# sch_substrate_board_pwr.net
KiCad netlist of a schematic drawn in Altium Designer
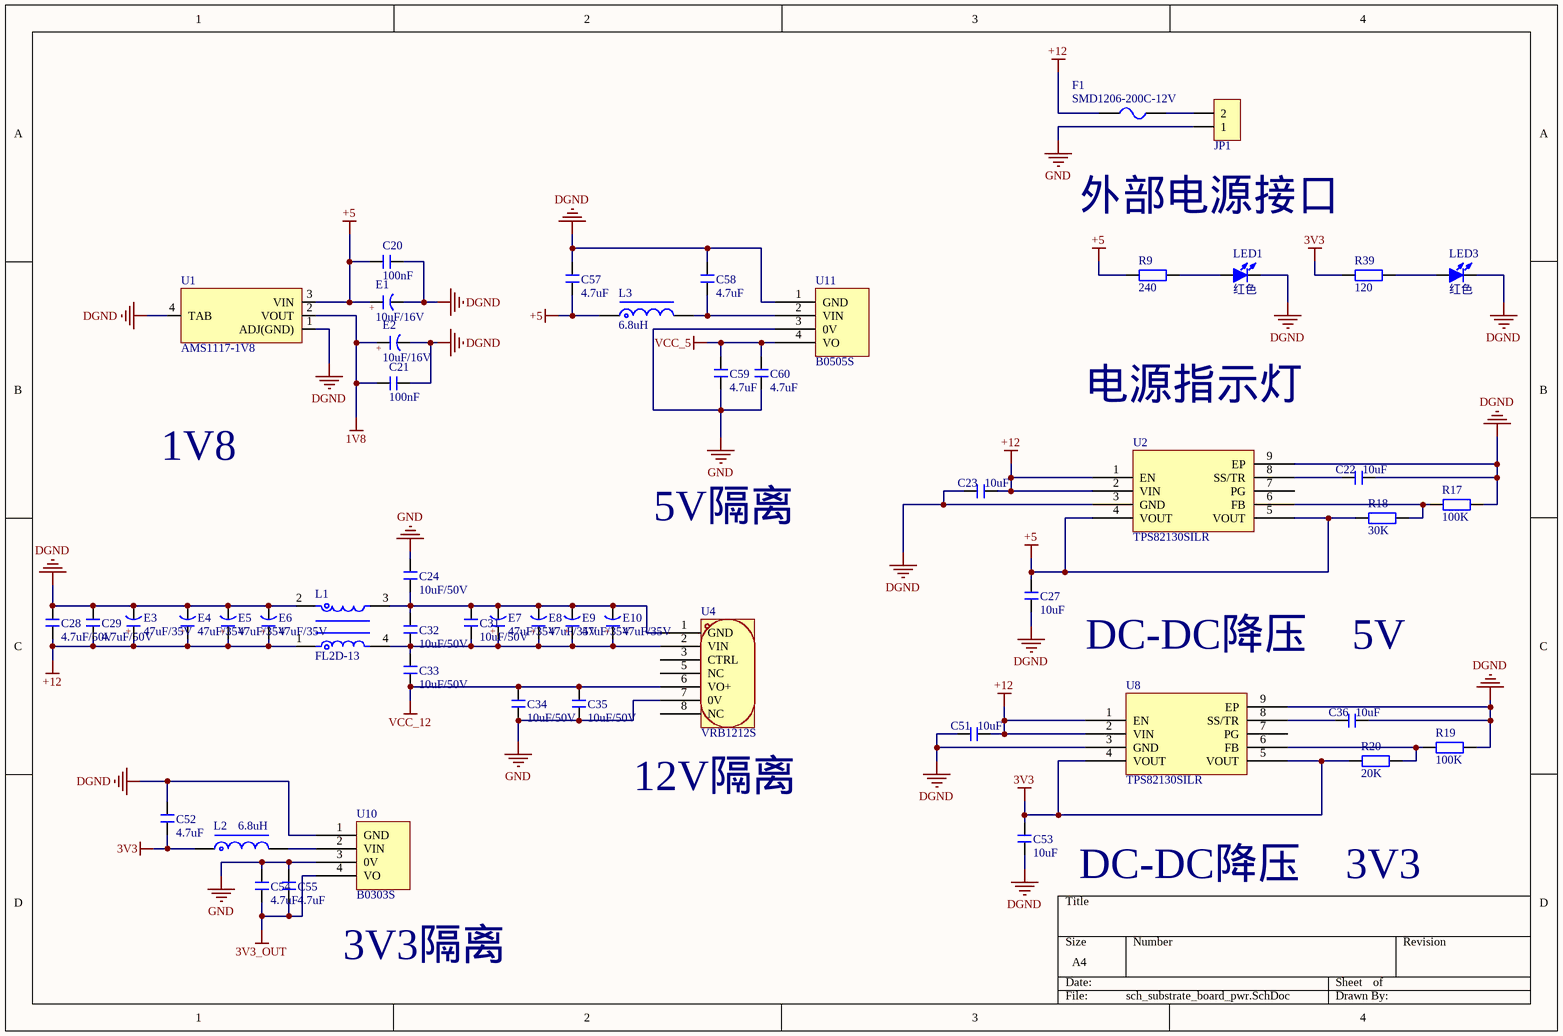
[diagram p0: sch_substrate_board_pwr.SchDoc]

(export (version "E")
  (design (tool "Eeschema 10.0.6"))
  (components
    (comp (ref "C20")
      (value "100nF")
      (footprint "C 0805_L")
      (description "贴片电容")
      (libsource (lib "0.1 - 电阻-电容-电感") (part "C"))
    )
    (comp (ref "C21")
      (value "100nF")
      (footprint "C 0805_L")
      (description "贴片电容")
      (libsource (lib "0.1 - 电阻-电容-电感") (part "C"))
    )
    (comp (ref "C22")
      (value "10uF")
      (footprint "C 0805_L")
      (description "贴片电容")
      (libsource (lib "0.1 - 电阻-电容-电感") (part "C"))
    )
    (comp (ref "C23")
      (value "10uF")
      (footprint "C 0805_L")
      (description "贴片电容")
      (libsource (lib "0.1 - 电阻-电容-电感") (part "C"))
    )
    (comp (ref "C24")
      (value "10uF/50V")
      (footprint "CAP-SMD_L8.0-W6.0-LS11.4")
      (description "贴片电容")
      (libsource (lib "0.1 - 电阻-电容-电感") (part "C"))
    )
    (comp (ref "C27")
      (value "10uF")
      (footprint "C 0805_L")
      (description "贴片电容")
      (libsource (lib "0.1 - 电阻-电容-电感") (part "C"))
    )
    (comp (ref "C28")
      (value "4.7uF/50V")
      (footprint "C 0805_L")
      (description "贴片电容")
      (libsource (lib "0.1 - 电阻-电容-电感") (part "C"))
    )
    (comp (ref "C29")
      (value "4.7uF/50V")
      (footprint "C 0805_L")
      (description "贴片电容")
      (libsource (lib "0.1 - 电阻-电容-电感") (part "C"))
    )
    (comp (ref "C31")
      (value "10uF/50V")
      (footprint "C 0805_L")
      (description "贴片电容")
      (libsource (lib "0.1 - 电阻-电容-电感") (part "C"))
    )
    (comp (ref "C32")
      (value "10uF/50V")
      (footprint "C 0805_L")
      (description "贴片电容")
      (libsource (lib "0.1 - 电阻-电容-电感") (part "C"))
    )
    (comp (ref "C33")
      (value "10uF/50V")
      (footprint "CAP-SMD_L8.0-W6.0-LS11.4")
      (description "贴片电容")
      (libsource (lib "0.1 - 电阻-电容-电感") (part "C"))
    )
    (comp (ref "C34")
      (value "10uF/50V")
      (footprint "C 0805_L")
      (description "贴片电容")
      (libsource (lib "0.1 - 电阻-电容-电感") (part "C"))
    )
    (comp (ref "C35")
      (value "10uF/50V")
      (footprint "C 0805_L")
      (description "贴片电容")
      (libsource (lib "0.1 - 电阻-电容-电感") (part "C"))
    )
    (comp (ref "C36")
      (value "10uF")
      (footprint "C 0805_L")
      (description "贴片电容")
      (libsource (lib "0.1 - 电阻-电容-电感") (part "C"))
    )
    (comp (ref "C51")
      (value "10uF")
      (footprint "C 0805_L")
      (description "贴片电容")
      (libsource (lib "0.1 - 电阻-电容-电感") (part "C"))
    )
    (comp (ref "C52")
      (value "4.7uF")
      (footprint "C 0805_L")
      (description "贴片电容")
      (libsource (lib "0.1 - 电阻-电容-电感") (part "C"))
    )
    (comp (ref "C53")
      (value "10uF")
      (footprint "C 0805_L")
      (description "贴片电容")
      (libsource (lib "0.1 - 电阻-电容-电感") (part "C"))
    )
    (comp (ref "C54")
      (value "4.7uF")
      (footprint "C 0805_L")
      (description "贴片电容")
      (libsource (lib "0.1 - 电阻-电容-电感") (part "C"))
    )
    (comp (ref "C55")
      (value "4.7uF")
      (footprint "C 0805_L")
      (description "贴片电容")
      (libsource (lib "0.1 - 电阻-电容-电感") (part "C"))
    )
    (comp (ref "C57")
      (value "4.7uF")
      (footprint "C 0805_L")
      (description "贴片电容")
      (libsource (lib "0.1 - 电阻-电容-电感") (part "C"))
    )
    (comp (ref "C58")
      (value "4.7uF")
      (footprint "C 0805_L")
      (description "贴片电容")
      (libsource (lib "0.1 - 电阻-电容-电感") (part "C"))
    )
    (comp (ref "C59")
      (value "4.7uF")
      (footprint "C 0805_L")
      (description "贴片电容")
      (libsource (lib "0.1 - 电阻-电容-电感") (part "C"))
    )
    (comp (ref "C60")
      (value "4.7uF")
      (footprint "C 0805_L")
      (description "贴片电容")
      (libsource (lib "0.1 - 电阻-电容-电感") (part "C"))
    )
    (comp (ref "E1")
      (value "10uF/16V")
      (footprint "CD A(3216)")
      (description "贴片钽电容")
      (libsource (lib "") (part "CT_1"))
    )
    (comp (ref "E2")
      (value "10uF/16V")
      (footprint "CD A(3216)")
      (description "贴片钽电容")
      (libsource (lib "") (part "CT_1"))
    )
    (comp (ref "E3")
      (value "47uF/35V")
      (footprint "CD D(7343)")
      (description "贴片钽电容")
      (libsource (lib "0.1 - 电阻-电容-电感") (part "CT"))
    )
    (comp (ref "E4")
      (value "47uF/35V")
      (footprint "CD D(7343)")
      (description "贴片钽电容")
      (libsource (lib "0.1 - 电阻-电容-电感") (part "CT"))
    )
    (comp (ref "E5")
      (value "47uF/35V")
      (footprint "CD D(7343)")
      (description "贴片钽电容")
      (libsource (lib "0.1 - 电阻-电容-电感") (part "CT"))
    )
    (comp (ref "E6")
      (value "47uF/35V")
      (footprint "CD D(7343)")
      (description "贴片钽电容")
      (libsource (lib "0.1 - 电阻-电容-电感") (part "CT"))
    )
    (comp (ref "E7")
      (value "47uF/35V")
      (footprint "CD D(7343)")
      (description "贴片钽电容")
      (libsource (lib "0.1 - 电阻-电容-电感") (part "CT"))
    )
    (comp (ref "E8")
      (value "47uF/35V")
      (footprint "CD D(7343)")
      (description "贴片钽电容")
      (libsource (lib "0.1 - 电阻-电容-电感") (part "CT"))
    )
    (comp (ref "E9")
      (value "47uF/35V")
      (footprint "CD D(7343)")
      (description "贴片钽电容")
      (libsource (lib "0.1 - 电阻-电容-电感") (part "CT"))
    )
    (comp (ref "E10")
      (value "47uF/35V")
      (footprint "CD D(7343)")
      (description "贴片钽电容")
      (libsource (lib "0.1 - 电阻-电容-电感") (part "CT"))
    )
    (comp (ref "F1")
      (value "SMD1206-200C-12V")
      (footprint "FU 1206")
      (description "贴片保险丝")
      (fields (field (name "版权归属") "封装库来自淘宝卖家 ID：黄晶宝石"))
      (libsource (lib "2.0 - 保险丝-晶振-光耦") (part "FU"))
    )
    (comp (ref "JP1")
      (value "HDR-1X2")
      (footprint "KF350-2P")
      (description "2P接插件")
      (fields (field (name "版权归属") "封装库来自淘宝卖家 ID：黄晶宝石"))
      (libsource (lib "5.5 - 接插件-脚距3.5") (part "Header 2"))
    )
    (comp (ref "L1")
      (value "FL2D-13")
      (footprint "FL2D-13")
      (description "共模滤波器")
      (libsource (lib "schlib_substrate") (part "FL2D-13"))
    )
    (comp (ref "L2")
      (value "6.8uH")
      (footprint "- duplicate")
      (description "功率磁环电感")
      (libsource (lib "0.1 - 电阻-电容-电感") (part "L-MR"))
    )
    (comp (ref "L3")
      (value "6.8uH")
      (footprint "- duplicate")
      (description "功率磁环电感")
      (libsource (lib "0.1 - 电阻-电容-电感") (part "L-MR"))
    )
    (comp (ref "LED1")
      (value "红色")
      (footprint "LED 0805R")
      (description "贴片LED")
      (fields (field (name "版权归属") "封装库来自淘宝 ID：黄晶宝石"))
      (libsource (lib "0.3 - LED发光二极管") (part "LED-SMD"))
    )
    (comp (ref "LED3")
      (value "红色")
      (footprint "LED 0805R")
      (description "贴片LED")
      (fields (field (name "版权归属") "封装库来自淘宝 ID：黄晶宝石"))
      (libsource (lib "0.3 - LED发光二极管") (part "LED-SMD"))
    )
    (comp (ref "R9")
      (value "240")
      (footprint "R 0805_L")
      (description "贴片电阻")
      (fields (field (name "版权归属") "来自淘宝 ID：黄晶宝石"))
      (libsource (lib "0.1 - 电阻-电容-电感") (part "R"))
    )
    (comp (ref "R17")
      (value "100K")
      (footprint "R 0805_L")
      (description "贴片电阻")
      (fields (field (name "版权归属") "来自淘宝 ID：黄晶宝石"))
      (libsource (lib "0.1 - 电阻-电容-电感") (part "R"))
    )
    (comp (ref "R18")
      (value "30K")
      (footprint "R 0805_L")
      (description "贴片电阻")
      (fields (field (name "版权归属") "来自淘宝 ID：黄晶宝石"))
      (libsource (lib "0.1 - 电阻-电容-电感") (part "R"))
    )
    (comp (ref "R19")
      (value "100K")
      (footprint "R 0805_L")
      (description "贴片电阻")
      (fields (field (name "版权归属") "来自淘宝 ID：黄晶宝石"))
      (libsource (lib "0.1 - 电阻-电容-电感") (part "R"))
    )
    (comp (ref "R20")
      (value "20K")
      (footprint "R 0805_L")
      (description "贴片电阻")
      (fields (field (name "版权归属") "来自淘宝 ID：黄晶宝石"))
      (libsource (lib "0.1 - 电阻-电容-电感") (part "R"))
    )
    (comp (ref "R39")
      (value "120")
      (footprint "R 0805_L")
      (description "贴片电阻")
      (fields (field (name "版权归属") "来自淘宝 ID：黄晶宝石"))
      (libsource (lib "0.1 - 电阻-电容-电感") (part "R"))
    )
    (comp (ref "U1")
      (value "AMS1117-1V8")
      (footprint "AMS1117")
      (description "电源稳压芯片")
      (libsource (lib "schlib_substrate") (part "AMS1117"))
    )
    (comp (ref "U2")
      (value "TPS82130SILR")
      (footprint "TPS82130SILR")
      (description "DC-DC")
      (libsource (lib "schlib_substrate") (part "TPS82130SILR"))
    )
    (comp (ref "U4")
      (value "VRB1212S")
      (footprint "VRB1205S")
      (description "电源隔离芯片")
      (libsource (lib "schlib_substrate") (part "VRB1205S-6WR31"))
    )
    (comp (ref "U8")
      (value "TPS82130SILR")
      (footprint "TPS82130SILR")
      (description "DC-DC")
      (libsource (lib "schlib_substrate") (part "TPS82130SILR"))
    )
    (comp (ref "U10")
      (value "B0303S")
      (footprint "B0303S")
      (description "IC")
      (libsource (lib "schlib_substrate") (part "B0303S"))
    )
    (comp (ref "U11")
      (value "B0505S")
      (footprint "B0505S")
      (description "电源隔离")
      (libsource (lib "schlib_substrate") (part "B0505S"))
    )
  )
  (nets
    (net (code "1") (name "+5") (class "Default")
      (node (ref "C20") (pin "1") (pinfunction "1_1") (pintype "passive"))
      (node (ref "C27") (pin "2") (pinfunction "2_2") (pintype "passive"))
      (node (ref "C57") (pin "1") (pinfunction "1_1") (pintype "passive"))
      (node (ref "E1") (pin "1") (pinfunction "A_1") (pintype "passive"))
      (node (ref "L3") (pin "1") (pinfunction "1_1") (pintype "passive"))
      (node (ref "R18") (pin "1") (pinfunction "1_1") (pintype "passive"))
      (node (ref "R9") (pin "2") (pinfunction "2_2") (pintype "passive"))
      (node (ref "U1") (pin "3") (pinfunction "VIN_3") (pintype "passive"))
      (node (ref "U2") (pin "4") (pinfunction "VOUT_4") (pintype "passive"))
      (node (ref "U2") (pin "5") (pinfunction "VOUT_5") (pintype "passive"))
    )
    (net (code "2") (name "+12") (class "Default")
      (node (ref "C23") (pin "2") (pinfunction "2_2") (pintype "passive"))
      (node (ref "C28") (pin "1") (pinfunction "1_1") (pintype "passive"))
      (node (ref "C29") (pin "1") (pinfunction "1_1") (pintype "passive"))
      (node (ref "C51") (pin "2") (pinfunction "2_2") (pintype "passive"))
      (node (ref "E3") (pin "1") (pinfunction "A_1") (pintype "passive"))
      (node (ref "E4") (pin "1") (pinfunction "A_1") (pintype "passive"))
      (node (ref "E5") (pin "1") (pinfunction "A_1") (pintype "passive"))
      (node (ref "E6") (pin "1") (pinfunction "A_1") (pintype "passive"))
      (node (ref "F1") (pin "1") (pinfunction "1_1") (pintype "passive"))
      (node (ref "L1") (pin "1") (pinfunction "1_1") (pintype "passive"))
      (node (ref "U2") (pin "1") (pinfunction "EN_1") (pintype "passive"))
      (node (ref "U2") (pin "2") (pinfunction "VIN_2") (pintype "passive"))
      (node (ref "U8") (pin "1") (pinfunction "EN_1") (pintype "passive"))
      (node (ref "U8") (pin "2") (pinfunction "VIN_2") (pintype "passive"))
    )
    (net (code "3") (name "1V8") (class "Default")
      (node (ref "C21") (pin "1") (pinfunction "1_1") (pintype "passive"))
      (node (ref "E2") (pin "1") (pinfunction "A_1") (pintype "passive"))
      (node (ref "U1") (pin "2") (pinfunction "VOUT_2") (pintype "passive"))
    )
    (net (code "4") (name "3V3") (class "Default")
      (node (ref "C52") (pin "2") (pinfunction "2_2") (pintype "passive"))
      (node (ref "C53") (pin "2") (pinfunction "2_2") (pintype "passive"))
      (node (ref "L2") (pin "1") (pinfunction "1_1") (pintype "passive"))
      (node (ref "R20") (pin "1") (pinfunction "1_1") (pintype "passive"))
      (node (ref "R39") (pin "2") (pinfunction "2_2") (pintype "passive"))
      (node (ref "U8") (pin "4") (pinfunction "VOUT_4") (pintype "passive"))
      (node (ref "U8") (pin "5") (pinfunction "VOUT_5") (pintype "passive"))
    )
    (net (code "5") (name "3V3_OUT") (class "Default")
      (node (ref "C54") (pin "2") (pinfunction "2_2") (pintype "passive"))
      (node (ref "C55") (pin "2") (pinfunction "2_2") (pintype "passive"))
      (node (ref "U10") (pin "4") (pinfunction "VO_4") (pintype "passive"))
    )
    (net (code "6") (name "DGND") (class "Default")
      (node (ref "C20") (pin "2") (pinfunction "2_2") (pintype "passive"))
      (node (ref "C21") (pin "2") (pinfunction "2_2") (pintype "passive"))
      (node (ref "C22") (pin "2") (pinfunction "2_2") (pintype "passive"))
      (node (ref "C23") (pin "1") (pinfunction "1_1") (pintype "passive"))
      (node (ref "C27") (pin "1") (pinfunction "1_1") (pintype "passive"))
      (node (ref "C28") (pin "2") (pinfunction "2_2") (pintype "passive"))
      (node (ref "C29") (pin "2") (pinfunction "2_2") (pintype "passive"))
      (node (ref "C36") (pin "2") (pinfunction "2_2") (pintype "passive"))
      (node (ref "C51") (pin "1") (pinfunction "1_1") (pintype "passive"))
      (node (ref "C52") (pin "1") (pinfunction "1_1") (pintype "passive"))
      (node (ref "C53") (pin "1") (pinfunction "1_1") (pintype "passive"))
      (node (ref "C57") (pin "2") (pinfunction "2_2") (pintype "passive"))
      (node (ref "C58") (pin "2") (pinfunction "2_2") (pintype "passive"))
      (node (ref "E1") (pin "2") (pinfunction "K_2") (pintype "passive"))
      (node (ref "E2") (pin "2") (pinfunction "K_2") (pintype "passive"))
      (node (ref "E3") (pin "2") (pinfunction "K_2") (pintype "passive"))
      (node (ref "E4") (pin "2") (pinfunction "K_2") (pintype "passive"))
      (node (ref "E5") (pin "2") (pinfunction "K_2") (pintype "passive"))
      (node (ref "E6") (pin "2") (pinfunction "K_2") (pintype "passive"))
      (node (ref "L1") (pin "2") (pinfunction "2_2") (pintype "passive"))
      (node (ref "LED1") (pin "2") (pinfunction "K_2") (pintype "passive"))
      (node (ref "LED3") (pin "2") (pinfunction "K_2") (pintype "passive"))
      (node (ref "R17") (pin "2") (pinfunction "2_2") (pintype "passive"))
      (node (ref "R19") (pin "2") (pinfunction "2_2") (pintype "passive"))
      (node (ref "U1") (pin "1") (pinfunction "ADJ(GND)_1") (pintype "passive"))
      (node (ref "U1") (pin "4") (pinfunction "TAB_4") (pintype "passive"))
      (node (ref "U10") (pin "1") (pinfunction "GND_1") (pintype "passive"))
      (node (ref "U11") (pin "1") (pinfunction "GND_1") (pintype "passive"))
      (node (ref "U2") (pin "3") (pinfunction "GND_3") (pintype "passive"))
      (node (ref "U2") (pin "9") (pinfunction "EP_9") (pintype "passive"))
      (node (ref "U8") (pin "3") (pinfunction "GND_3") (pintype "passive"))
      (node (ref "U8") (pin "9") (pinfunction "EP_9") (pintype "passive"))
    )
    (net (code "7") (name "GND") (class "Default")
      (node (ref "C24") (pin "2") (pinfunction "2_2") (pintype "passive"))
      (node (ref "C34") (pin "1") (pinfunction "1_1") (pintype "passive"))
      (node (ref "C35") (pin "1") (pinfunction "1_1") (pintype "passive"))
      (node (ref "C54") (pin "1") (pinfunction "1_1") (pintype "passive"))
      (node (ref "C55") (pin "1") (pinfunction "1_1") (pintype "passive"))
      (node (ref "C59") (pin "2") (pinfunction "2_2") (pintype "passive"))
      (node (ref "C60") (pin "2") (pinfunction "2_2") (pintype "passive"))
      (node (ref "JP1") (pin "1") (pinfunction "1_1") (pintype "passive"))
      (node (ref "U10") (pin "3") (pinfunction "0V_3") (pintype "passive"))
      (node (ref "U11") (pin "3") (pinfunction "0V_3") (pintype "passive"))
      (node (ref "U4") (pin "7") (pinfunction "0V_7") (pintype "passive"))
    )
    (net (code "8") (name "Net-(E10-A)") (class "Default")
      (node (ref "C31") (pin "1") (pinfunction "1_1") (pintype "passive"))
      (node (ref "C32") (pin "1") (pinfunction "1_1") (pintype "passive"))
      (node (ref "C33") (pin "1") (pinfunction "1_1") (pintype "passive"))
      (node (ref "E10") (pin "1") (pinfunction "A_1") (pintype "passive"))
      (node (ref "E7") (pin "1") (pinfunction "A_1") (pintype "passive"))
      (node (ref "E8") (pin "1") (pinfunction "A_1") (pintype "passive"))
      (node (ref "E9") (pin "1") (pinfunction "A_1") (pintype "passive"))
      (node (ref "L1") (pin "4") (pinfunction "4_4") (pintype "passive"))
      (node (ref "U4") (pin "2") (pinfunction "VIN_2") (pintype "passive"))
    )
    (net (code "9") (name "Net-(E10-K)") (class "Default")
      (node (ref "C24") (pin "1") (pinfunction "1_1") (pintype "passive"))
      (node (ref "C31") (pin "2") (pinfunction "2_2") (pintype "passive"))
      (node (ref "C32") (pin "2") (pinfunction "2_2") (pintype "passive"))
      (node (ref "E10") (pin "2") (pinfunction "K_2") (pintype "passive"))
      (node (ref "E7") (pin "2") (pinfunction "K_2") (pintype "passive"))
      (node (ref "E8") (pin "2") (pinfunction "K_2") (pintype "passive"))
      (node (ref "E9") (pin "2") (pinfunction "K_2") (pintype "passive"))
      (node (ref "L1") (pin "3") (pinfunction "3_3") (pintype "passive"))
      (node (ref "U4") (pin "1") (pinfunction "GND_1") (pintype "passive"))
    )
    (net (code "10") (name "Net-(F1-Pad2)") (class "Default")
      (node (ref "F1") (pin "2") (pinfunction "2_2") (pintype "passive"))
      (node (ref "JP1") (pin "2") (pinfunction "2_2") (pintype "passive"))
    )
    (net (code "11") (name "Net-(LED1-A)") (class "Default")
      (node (ref "LED1") (pin "1") (pinfunction "A_1") (pintype "passive"))
      (node (ref "R9") (pin "1") (pinfunction "1_1") (pintype "passive"))
    )
    (net (code "12") (name "Net-(LED3-A)") (class "Default")
      (node (ref "LED3") (pin "1") (pinfunction "A_1") (pintype "passive"))
      (node (ref "R39") (pin "1") (pinfunction "1_1") (pintype "passive"))
    )
    (net (code "13") (name "Net-(U2-FB)") (class "Default")
      (node (ref "R17") (pin "1") (pinfunction "1_1") (pintype "passive"))
      (node (ref "R18") (pin "2") (pinfunction "2_2") (pintype "passive"))
      (node (ref "U2") (pin "6") (pinfunction "FB_6") (pintype "passive"))
    )
    (net (code "14") (name "Net-(U2-SS{slash}TR)") (class "Default")
      (node (ref "C22") (pin "1") (pinfunction "1_1") (pintype "passive"))
      (node (ref "U2") (pin "8") (pinfunction "SS/TR_8") (pintype "passive"))
    )
    (net (code "15") (name "Net-(U8-FB)") (class "Default")
      (node (ref "R19") (pin "1") (pinfunction "1_1") (pintype "passive"))
      (node (ref "R20") (pin "2") (pinfunction "2_2") (pintype "passive"))
      (node (ref "U8") (pin "6") (pinfunction "FB_6") (pintype "passive"))
    )
    (net (code "16") (name "Net-(U8-SS{slash}TR)") (class "Default")
      (node (ref "C36") (pin "1") (pinfunction "1_1") (pintype "passive"))
      (node (ref "U8") (pin "8") (pinfunction "SS/TR_8") (pintype "passive"))
    )
    (net (code "17") (name "Net-(U10-VIN)") (class "Default")
      (node (ref "L2") (pin "2") (pinfunction "2_2") (pintype "passive"))
      (node (ref "U10") (pin "2") (pinfunction "VIN_2") (pintype "passive"))
    )
    (net (code "18") (name "Net-(U11-VIN)") (class "Default")
      (node (ref "C58") (pin "1") (pinfunction "1_1") (pintype "passive"))
      (node (ref "L3") (pin "2") (pinfunction "2_2") (pintype "passive"))
      (node (ref "U11") (pin "2") (pinfunction "VIN_2") (pintype "passive"))
    )
    (net (code "19") (name "VCC_5") (class "Default")
      (node (ref "C59") (pin "1") (pinfunction "1_1") (pintype "passive"))
      (node (ref "C60") (pin "1") (pinfunction "1_1") (pintype "passive"))
      (node (ref "U11") (pin "4") (pinfunction "VO_4") (pintype "passive"))
    )
    (net (code "20") (name "VCC_12") (class "Default")
      (node (ref "C33") (pin "2") (pinfunction "2_2") (pintype "passive"))
      (node (ref "C34") (pin "2") (pinfunction "2_2") (pintype "passive"))
      (node (ref "C35") (pin "2") (pinfunction "2_2") (pintype "passive"))
      (node (ref "U4") (pin "6") (pinfunction "VO+_6") (pintype "passive"))
    )
    (net (code "21") (name "unconnected-(U2-PG-Pad7)") (class "Default")
      (node (ref "U2") (pin "7") (pinfunction "PG_7") (pintype "passive"))
    )
    (net (code "22") (name "unconnected-(U4-CTRL-Pad3)") (class "Default")
      (node (ref "U4") (pin "3") (pinfunction "CTRL_3") (pintype "passive"))
    )
    (net (code "23") (name "unconnected-(U4-NC-Pad5)") (class "Default")
      (node (ref "U4") (pin "5") (pinfunction "NC_5") (pintype "passive"))
    )
    (net (code "24") (name "unconnected-(U4-NC-Pad8)") (class "Default")
      (node (ref "U4") (pin "8") (pinfunction "NC_8") (pintype "passive"))
    )
    (net (code "25") (name "unconnected-(U8-PG-Pad7)") (class "Default")
      (node (ref "U8") (pin "7") (pinfunction "PG_7") (pintype "passive"))
    )
  )
)
